# 26_LMS3_RX2_BB_ADC.net
KiCad netlist of a schematic drawn in Altium Designer
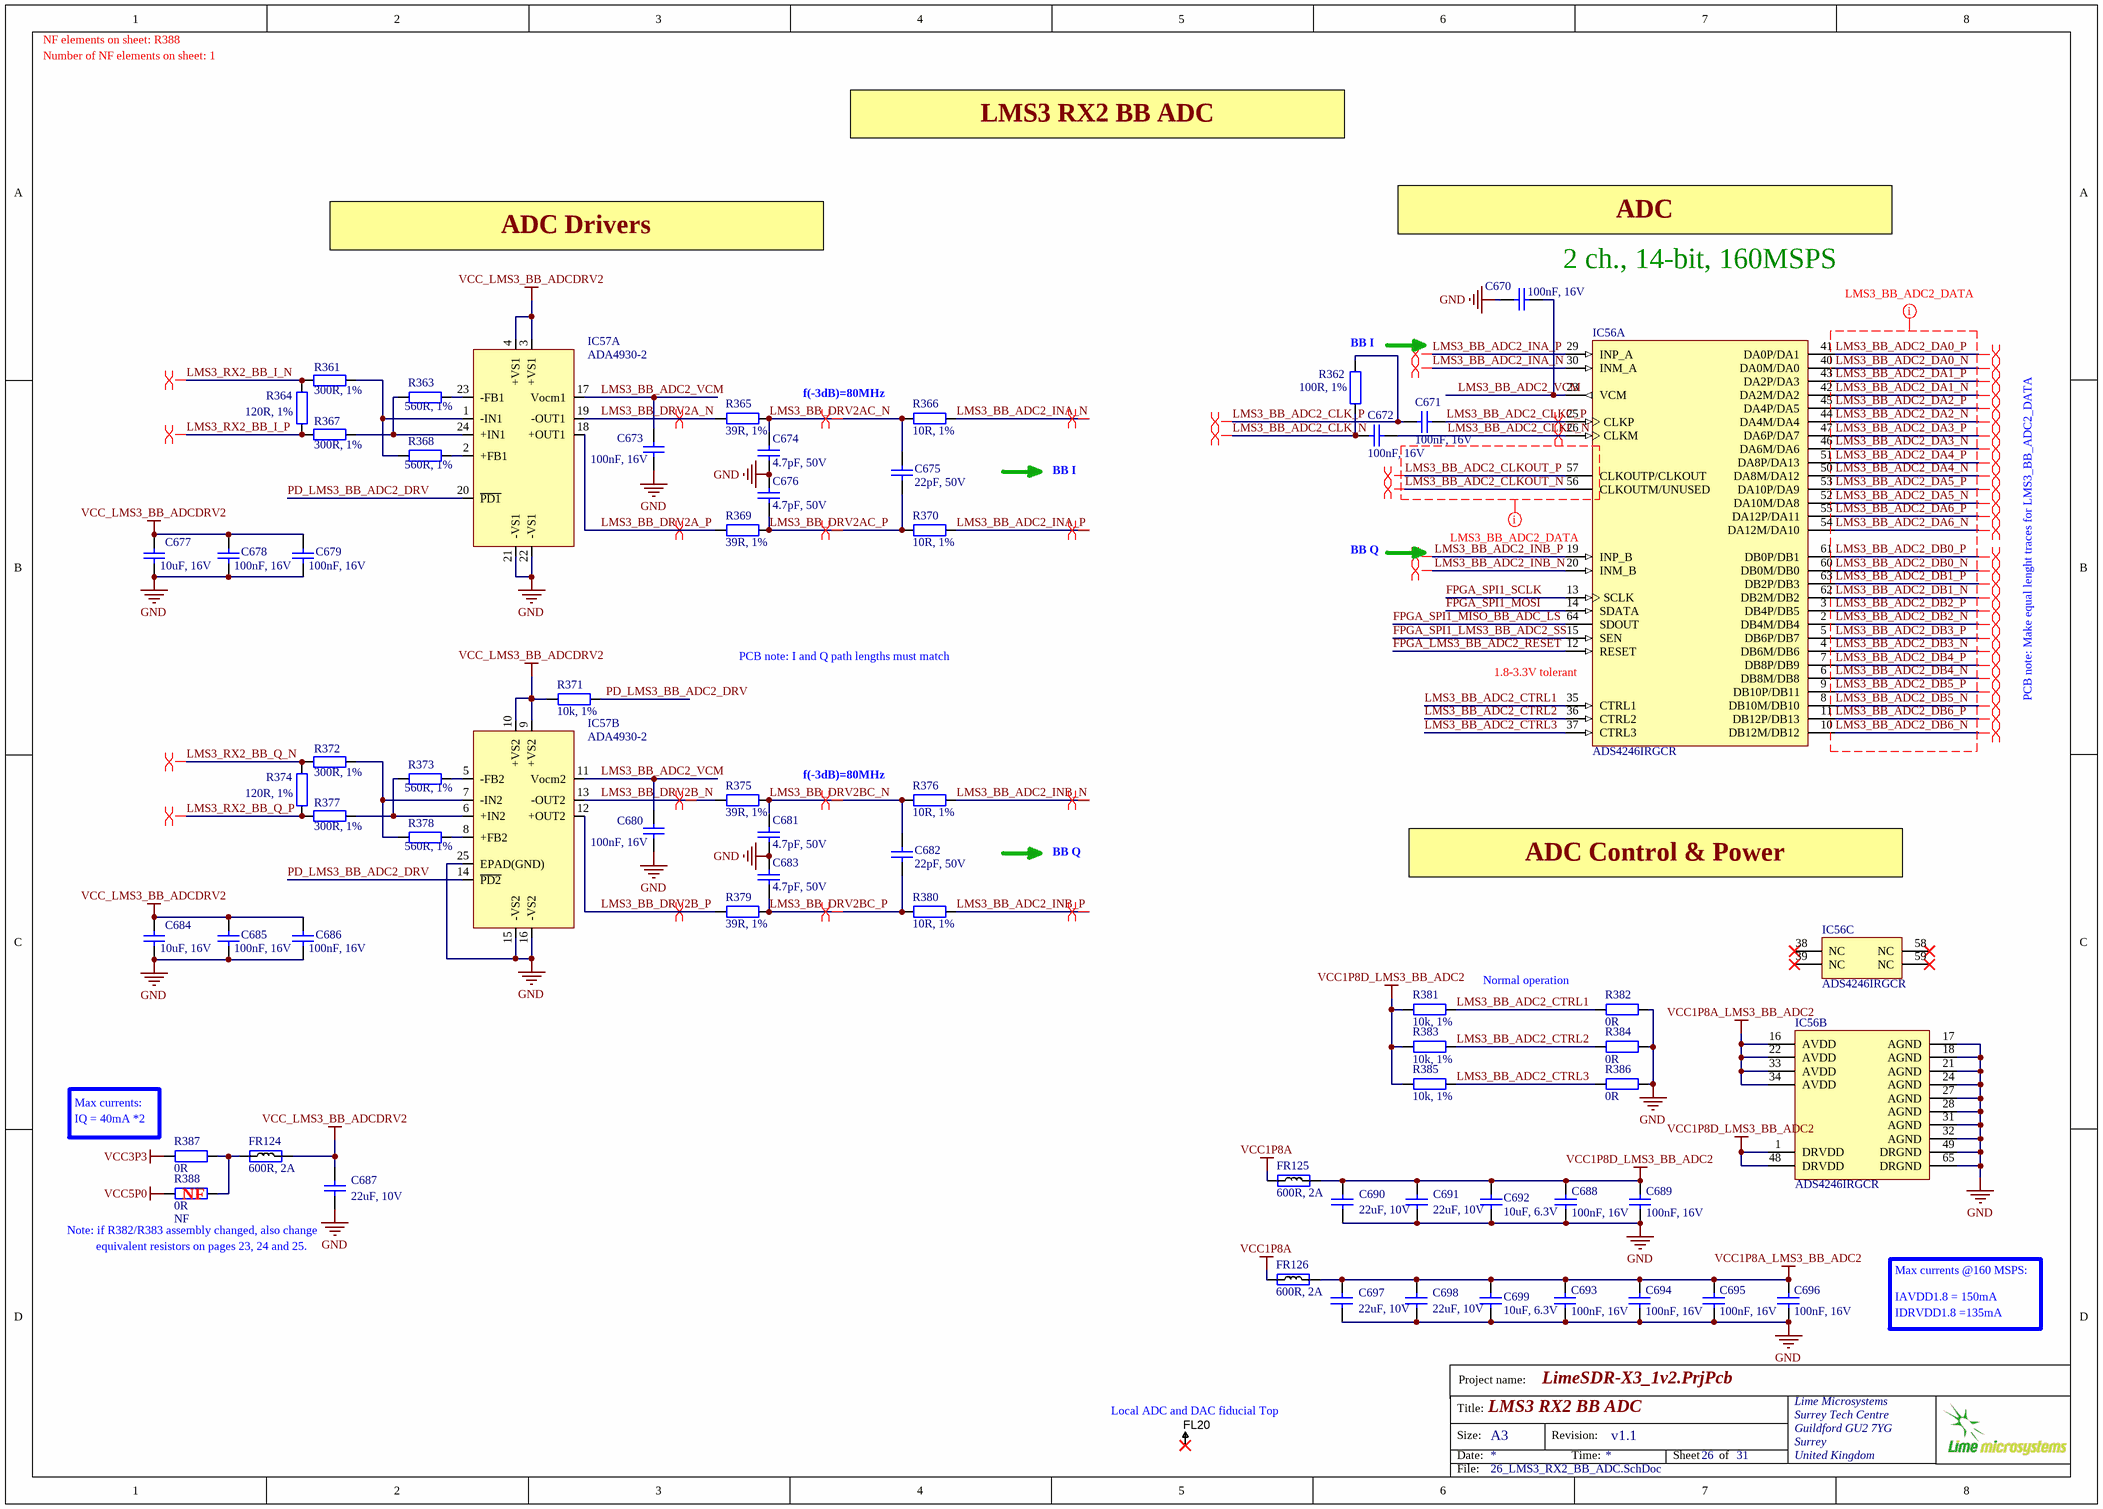
[diagram p0: 26_LMS3_RX2_BB_ADC.SchDoc]

(export (version "E")
  (design (tool "Eeschema 10.0.6"))
  (components
    (comp (ref "C670")
      (value "100nF, 16V")
      (footprint "CAP0402")
      (fields (field (name "TOLERANCE") "10 %") (field (name "MANUFACTURER") "Murata Electronics"))
      (libsource (lib "") (part "Cap_0603_3"))
    )
    (comp (ref "C671")
      (value "100nF, 16V")
      (footprint "CAP0402")
      (fields (field (name "TOLERANCE") "10 %") (field (name "MANUFACTURER") "Murata Electronics"))
      (libsource (lib "") (part "Cap_0603_3"))
    )
    (comp (ref "C672")
      (value "100nF, 16V")
      (footprint "CAP0402")
      (fields (field (name "TOLERANCE") "10 %") (field (name "MANUFACTURER") "Murata Electronics"))
      (libsource (lib "LimeFPGAboard_schLib") (part "Cap_0603"))
    )
    (comp (ref "C673")
      (value "100nF, 16V")
      (footprint "CAP0402")
      (fields (field (name "TOLERANCE") "10 %") (field (name "MANUFACTURER") "Murata Electronics"))
      (libsource (lib "LimeFPGAboard_schLib") (part "Cap_0603"))
    )
    (comp (ref "C674")
      (value "4.7pF, 50V")
      (footprint "CAP0402")
      (fields (field (name "MANUFACTURER") "MURATA"))
      (libsource (lib "") (part "Cap_0402_1"))
    )
    (comp (ref "C675")
      (value "22pF, 50V")
      (footprint "CAP0402")
      (fields (field (name "TOLERANCE") "±5%") (field (name "MANUFACTURER") "Yageo"))
      (libsource (lib "LimeMicroAltiumLib_schLib") (part "Cap_0402"))
    )
    (comp (ref "C676")
      (value "4.7pF, 50V")
      (footprint "CAP0402")
      (fields (field (name "MANUFACTURER") "MURATA"))
      (libsource (lib "") (part "Cap_0402_1"))
    )
    (comp (ref "C677")
      (value "10uF, 16V")
      (footprint "CAP0603")
      (fields (field (name "MANUFACTURER") "Yageo") (field (name "TOLERANCE") "±20%"))
      (libsource (lib "LimeMicroAltiumLib_schLib") (part "Cap_0603"))
    )
    (comp (ref "C678")
      (value "100nF, 16V")
      (footprint "CAP0402")
      (fields (field (name "TOLERANCE") "10 %") (field (name "MANUFACTURER") "Murata Electronics"))
      (libsource (lib "LimeFPGAboard_schLib") (part "Cap_0603"))
    )
    (comp (ref "C679")
      (value "100nF, 16V")
      (footprint "CAP0402")
      (fields (field (name "TOLERANCE") "10 %") (field (name "MANUFACTURER") "Murata Electronics"))
      (libsource (lib "LimeFPGAboard_schLib") (part "Cap_0603"))
    )
    (comp (ref "C680")
      (value "100nF, 16V")
      (footprint "CAP0402")
      (fields (field (name "TOLERANCE") "10 %") (field (name "MANUFACTURER") "Murata Electronics"))
      (libsource (lib "") (part "Cap_0603_6"))
    )
    (comp (ref "C681")
      (value "4.7pF, 50V")
      (footprint "CAP0402")
      (fields (field (name "MANUFACTURER") "MURATA"))
      (libsource (lib "") (part "Cap_0402_1"))
    )
    (comp (ref "C682")
      (value "22pF, 50V")
      (footprint "CAP0402")
      (fields (field (name "TOLERANCE") "±5%") (field (name "MANUFACTURER") "Yageo"))
      (libsource (lib "LimeMicroAltiumLib_schLib") (part "Cap_0402"))
    )
    (comp (ref "C683")
      (value "4.7pF, 50V")
      (footprint "CAP0402")
      (fields (field (name "MANUFACTURER") "MURATA"))
      (libsource (lib "") (part "Cap_0402_1"))
    )
    (comp (ref "C684")
      (value "10uF, 16V")
      (footprint "CAP0603")
      (fields (field (name "MANUFACTURER") "Yageo") (field (name "TOLERANCE") "±20%"))
      (libsource (lib "LimeMicroAltiumLib_schLib") (part "Cap_0603"))
    )
    (comp (ref "C685")
      (value "100nF, 16V")
      (footprint "CAP0402")
      (fields (field (name "TOLERANCE") "10 %") (field (name "MANUFACTURER") "Murata Electronics"))
      (libsource (lib "LimeFPGAboard_schLib") (part "Cap_0603"))
    )
    (comp (ref "C686")
      (value "100nF, 16V")
      (footprint "CAP0402")
      (fields (field (name "TOLERANCE") "10 %") (field (name "MANUFACTURER") "Murata Electronics"))
      (libsource (lib "LimeFPGAboard_schLib") (part "Cap_0603"))
    )
    (comp (ref "C687")
      (value "22uF, 10V")
      (footprint "CAP0603")
      (fields (field (name "TOLERANCE") "20 %") (field (name "MANUFACTURER") "TDK Corporation"))
      (libsource (lib "") (part "Cap_0603_7"))
    )
    (comp (ref "C688")
      (value "100nF, 16V")
      (footprint "CAP0402")
      (fields (field (name "TOLERANCE") "10 %") (field (name "MANUFACTURER") "Murata Electronics"))
      (libsource (lib "") (part "Cap_0603_2"))
    )
    (comp (ref "C689")
      (value "100nF, 16V")
      (footprint "CAP0402")
      (fields (field (name "TOLERANCE") "10 %") (field (name "MANUFACTURER") "Murata Electronics"))
      (libsource (lib "") (part "Cap_0603_2"))
    )
    (comp (ref "C690")
      (value "22uF, 10V")
      (footprint "CAP0603")
      (fields (field (name "TOLERANCE") "20 %") (field (name "MANUFACTURER") "TDK Corporation"))
      (libsource (lib "") (part "Cap_0603_2"))
    )
    (comp (ref "C691")
      (value "22uF, 10V")
      (footprint "CAP0603")
      (fields (field (name "TOLERANCE") "20 %") (field (name "MANUFACTURER") "TDK Corporation"))
      (libsource (lib "") (part "Cap_0603_2"))
    )
    (comp (ref "C692")
      (value "10uF, 6.3V")
      (footprint "CAP0603")
      (fields (field (name "TOLERANCE") "±20%") (field (name "MANUFACTURER") "Yageo"))
      (libsource (lib "") (part "Cap_0603_5"))
    )
    (comp (ref "C693")
      (value "100nF, 16V")
      (footprint "CAP0402")
      (fields (field (name "TOLERANCE") "10 %") (field (name "MANUFACTURER") "Murata Electronics"))
      (libsource (lib "") (part "Cap_0603_1"))
    )
    (comp (ref "C694")
      (value "100nF, 16V")
      (footprint "CAP0402")
      (fields (field (name "TOLERANCE") "10 %") (field (name "MANUFACTURER") "Murata Electronics"))
      (libsource (lib "") (part "Cap_0603_1"))
    )
    (comp (ref "C695")
      (value "100nF, 16V")
      (footprint "CAP0402")
      (fields (field (name "TOLERANCE") "10 %") (field (name "MANUFACTURER") "Murata Electronics"))
      (libsource (lib "") (part "Cap_0603_1"))
    )
    (comp (ref "C696")
      (value "100nF, 16V")
      (footprint "CAP0402")
      (fields (field (name "TOLERANCE") "10 %") (field (name "MANUFACTURER") "Murata Electronics"))
      (libsource (lib "") (part "Cap_0603_1"))
    )
    (comp (ref "C697")
      (value "22uF, 10V")
      (footprint "CAP0603")
      (fields (field (name "TOLERANCE") "20 %") (field (name "MANUFACTURER") "TDK Corporation"))
      (libsource (lib "") (part "Cap_0603_1"))
    )
    (comp (ref "C698")
      (value "22uF, 10V")
      (footprint "CAP0603")
      (fields (field (name "TOLERANCE") "20 %") (field (name "MANUFACTURER") "TDK Corporation"))
      (libsource (lib "") (part "Cap_0603_1"))
    )
    (comp (ref "C699")
      (value "10uF, 6.3V")
      (footprint "CAP0603")
      (fields (field (name "TOLERANCE") "±20%") (field (name "MANUFACTURER") "Yageo"))
      (libsource (lib "") (part "Cap_0603_4"))
    )
    (comp (ref "FL20")
      (value "Fiducial")
      (footprint "Fiducial_local")
      (libsource (lib "LimeMicroAltiumLib_schLib") (part "Fiducial"))
    )
    (comp (ref "FR124")
      (value "600R, 2A")
      (footprint "RES0805")
      (fields (field (name "MANUFACTURER") "TDK Corporation"))
      (libsource (lib "LimeMicroAltiumLib_schLib") (part "Ferrite"))
    )
    (comp (ref "FR125")
      (value "600R, 2A")
      (footprint "RES0805")
      (fields (field (name "MANUFACTURER") "TDK Corporation"))
      (libsource (lib "LimeFPGAboard_schLib") (part "Ferrite"))
    )
    (comp (ref "FR126")
      (value "600R, 2A")
      (footprint "RES0805")
      (fields (field (name "MANUFACTURER") "TDK Corporation"))
      (libsource (lib "LimeFPGAboard_schLib") (part "Ferrite"))
    )
    (comp (ref "IC56")
      (value "ADS4246IRGCR")
      (footprint "TI-RGC64-7400X7400TP_V")
      (description "14-Bit 160 MSPS Dual Low Power ADC, -40 to 85 degC, 64-pin QFN (RGC64), Green (RoHS & no Sb/Br)")
      (fields (field (name "MANUFACTURER") "Texas Instruments"))
      (libsource (lib "") (part "ADS4246IRGCR_1"))
    )
    (comp (ref "IC57")
      (value "ADA4930-2")
      (footprint "ADA4930-2_LFCSP-24")
      (fields (field (name "MANUFACTURER") "Analog Devices Inc."))
      (libsource (lib "") (part "ADA4930-2_1"))
    )
    (comp (ref "R361")
      (value "300R, 1%")
      (footprint "RES0402")
      (fields (field (name "TOLERANCE") "±1%") (field (name "MANUFACTURER") "Vishay Dale"))
      (libsource (lib "") (part "Res_0402_1"))
    )
    (comp (ref "R362")
      (value "100R, 1%")
      (footprint "RES0402")
      (fields (field (name "TOLERANCE") "±1%") (field (name "MANUFACTURER") "Stackpole Electronics Inc."))
      (libsource (lib "") (part "Res_0402_1"))
    )
    (comp (ref "R363")
      (value "560R, 1%")
      (footprint "RES0402")
      (fields (field (name "TOLERANCE") "±1%") (field (name "MANUFACTURER") "Vishay Dale"))
      (libsource (lib "") (part "Res_0402_1"))
    )
    (comp (ref "R364")
      (value "120R, 1%")
      (footprint "RES0402")
      (fields (field (name "MANUFACTURER") "Yageo") (field (name "TOLERANCE") "1%"))
      (libsource (lib "LimeFPGAboard_schLib") (part "Res_0402"))
    )
    (comp (ref "R365")
      (value "39R, 1%")
      (footprint "RES0402")
      (fields (field (name "MANUFACTURER") "Yageo") (field (name "TOLERANCE") "1%"))
      (libsource (lib "LimeMicroAltiumLib_schLib") (part "Res_0402"))
    )
    (comp (ref "R366")
      (value "10R, 1%")
      (footprint "RES0402")
      (fields (field (name "TOLERANCE") "1%"))
      (libsource (lib "LimeMicroAltiumLib_schLib") (part "Res_0402"))
    )
    (comp (ref "R367")
      (value "300R, 1%")
      (footprint "RES0402")
      (fields (field (name "TOLERANCE") "±1%") (field (name "MANUFACTURER") "Vishay Dale"))
      (libsource (lib "") (part "Res_0402_1"))
    )
    (comp (ref "R368")
      (value "560R, 1%")
      (footprint "RES0402")
      (fields (field (name "TOLERANCE") "±1%") (field (name "MANUFACTURER") "Vishay Dale"))
      (libsource (lib "") (part "Res_0402_1"))
    )
    (comp (ref "R369")
      (value "39R, 1%")
      (footprint "RES0402")
      (fields (field (name "MANUFACTURER") "Yageo") (field (name "TOLERANCE") "1%"))
      (libsource (lib "LimeMicroAltiumLib_schLib") (part "Res_0402"))
    )
    (comp (ref "R370")
      (value "10R, 1%")
      (footprint "RES0402")
      (fields (field (name "TOLERANCE") "1%"))
      (libsource (lib "LimeMicroAltiumLib_schLib") (part "Res_0402"))
    )
    (comp (ref "R371")
      (value "10k, 1%")
      (footprint "RES0402")
      (fields (field (name "MANUFACTURER") "Yageo") (field (name "TOLERANCE") "±1%"))
      (libsource (lib "LimeMicroAltiumLib_schLib") (part "Res_0402"))
    )
    (comp (ref "R372")
      (value "300R, 1%")
      (footprint "RES0402")
      (fields (field (name "TOLERANCE") "±1%") (field (name "MANUFACTURER") "Vishay Dale"))
      (libsource (lib "") (part "Res_0402_1"))
    )
    (comp (ref "R373")
      (value "560R, 1%")
      (footprint "RES0402")
      (fields (field (name "TOLERANCE") "±1%") (field (name "MANUFACTURER") "Vishay Dale"))
      (libsource (lib "") (part "Res_0402_1"))
    )
    (comp (ref "R374")
      (value "120R, 1%")
      (footprint "RES0402")
      (fields (field (name "MANUFACTURER") "Yageo") (field (name "TOLERANCE") "1%"))
      (libsource (lib "LimeFPGAboard_schLib") (part "Res_0402"))
    )
    (comp (ref "R375")
      (value "39R, 1%")
      (footprint "RES0402")
      (fields (field (name "MANUFACTURER") "Yageo") (field (name "TOLERANCE") "1%"))
      (libsource (lib "LimeMicroAltiumLib_schLib") (part "Res_0402"))
    )
    (comp (ref "R376")
      (value "10R, 1%")
      (footprint "RES0402")
      (fields (field (name "TOLERANCE") "1%"))
      (libsource (lib "LimeMicroAltiumLib_schLib") (part "Res_0402"))
    )
    (comp (ref "R377")
      (value "300R, 1%")
      (footprint "RES0402")
      (fields (field (name "TOLERANCE") "±1%") (field (name "MANUFACTURER") "Vishay Dale"))
      (libsource (lib "") (part "Res_0402_1"))
    )
    (comp (ref "R378")
      (value "560R, 1%")
      (footprint "RES0402")
      (fields (field (name "TOLERANCE") "±1%") (field (name "MANUFACTURER") "Vishay Dale"))
      (libsource (lib "") (part "Res_0402_1"))
    )
    (comp (ref "R379")
      (value "39R, 1%")
      (footprint "RES0402")
      (fields (field (name "MANUFACTURER") "Yageo") (field (name "TOLERANCE") "1%"))
      (libsource (lib "LimeMicroAltiumLib_schLib") (part "Res_0402"))
    )
    (comp (ref "R380")
      (value "10R, 1%")
      (footprint "RES0402")
      (fields (field (name "TOLERANCE") "1%"))
      (libsource (lib "LimeMicroAltiumLib_schLib") (part "Res_0402"))
    )
    (comp (ref "R381")
      (value "10k, 1%")
      (footprint "RES0402")
      (fields (field (name "MANUFACTURER") "Yageo") (field (name "TOLERANCE") "±1%"))
      (libsource (lib "LimeMicroAltiumLib_schLib") (part "Res_0402"))
    )
    (comp (ref "R382")
      (value "0R")
      (footprint "RES0402")
      (fields (field (name "MANUFACTURER") "Yageo"))
      (libsource (lib "") (part "Res_0402_1"))
    )
    (comp (ref "R383")
      (value "10k, 1%")
      (footprint "RES0402")
      (fields (field (name "MANUFACTURER") "Yageo") (field (name "TOLERANCE") "±1%"))
      (libsource (lib "LimeMicroAltiumLib_schLib") (part "Res_0402"))
    )
    (comp (ref "R384")
      (value "0R")
      (footprint "RES0402")
      (fields (field (name "MANUFACTURER") "Yageo"))
      (libsource (lib "") (part "Res_0402_1"))
    )
    (comp (ref "R385")
      (value "10k, 1%")
      (footprint "RES0402")
      (fields (field (name "MANUFACTURER") "Yageo") (field (name "TOLERANCE") "±1%"))
      (libsource (lib "LimeMicroAltiumLib_schLib") (part "Res_0402"))
    )
    (comp (ref "R386")
      (value "0R")
      (footprint "RES0402")
      (fields (field (name "MANUFACTURER") "Yageo"))
      (libsource (lib "") (part "Res_0402_1"))
    )
    (comp (ref "R387")
      (value "0R")
      (footprint "RES0402")
      (fields (field (name "MANUFACTURER") "Yageo") (field (name "TOLERANCE") "Jumper"))
      (libsource (lib "LimeMicroAltiumLib_schLib") (part "Res_0402"))
    )
    (comp (ref "R388")
      (value "0R")
      (footprint "RES0402")
      (fields
        (field (name "ASSEMBLY INFO") "NF")
        (field (name "MANUFACTURER") "Yageo")
        (field (name "TOLERANCE") "Jumper")
      )
      (libsource (lib "LimeMicroAltiumLib_schLib") (part "Res_0402"))
    )
  )
  (nets
    (net (code "1") (name "/FPGA_LMS3_BB_ADC2_RESET") (class "Default")
      (node (ref "IC56") (pin "12") (pinfunction "RESET_12") (pintype "input"))
    )
    (net (code "2") (name "/FPGA_SPI1_LMS3_BB_ADC2_SS") (class "Default")
      (node (ref "IC56") (pin "15") (pinfunction "SEN_15") (pintype "input"))
    )
    (net (code "3") (name "/FPGA_SPI1_MISO_BB_ADC_LS") (class "Default")
      (node (ref "IC56") (pin "64") (pinfunction "SDOUT_64") (pintype "tri_state"))
    )
    (net (code "4") (name "/FPGA_SPI1_MOSI") (class "Default")
      (node (ref "IC56") (pin "14") (pinfunction "SDATA_14") (pintype "input"))
    )
    (net (code "5") (name "/FPGA_SPI1_SCLK") (class "Default")
      (node (ref "IC56") (pin "13") (pinfunction "SCLK_13") (pintype "input"))
    )
    (net (code "6") (name "/LMS3_BB_ADC2_CLKC_N") (class "Default")
      (node (ref "C672") (pin "1") (pinfunction "1_1") (pintype "passive"))
      (node (ref "IC56") (pin "26") (pinfunction "CLKM_26") (pintype "input"))
    )
    (net (code "7") (name "/LMS3_BB_ADC2_CLKC_P") (class "Default")
      (node (ref "C671") (pin "1") (pinfunction "1_1") (pintype "passive"))
      (node (ref "IC56") (pin "25") (pinfunction "CLKP_25") (pintype "input"))
    )
    (net (code "8") (name "/LMS3_BB_ADC2_CLKOUT_N") (class "Default")
      (node (ref "IC56") (pin "56") (pinfunction "CLKOUTM/UNUSED_56") (pintype "tri_state"))
    )
    (net (code "9") (name "/LMS3_BB_ADC2_CLKOUT_P") (class "Default")
      (node (ref "IC56") (pin "57") (pinfunction "CLKOUTP/CLKOUT_57") (pintype "tri_state"))
    )
    (net (code "10") (name "/LMS3_BB_ADC2_CLK_N") (class "Default")
      (node (ref "C672") (pin "2") (pinfunction "2_2") (pintype "passive"))
      (node (ref "R362") (pin "1") (pinfunction "1_1") (pintype "passive"))
    )
    (net (code "11") (name "/LMS3_BB_ADC2_CLK_P") (class "Default")
      (node (ref "C671") (pin "2") (pinfunction "2_2") (pintype "passive"))
      (node (ref "R362") (pin "2") (pinfunction "2_2") (pintype "passive"))
    )
    (net (code "12") (name "/LMS3_BB_ADC2_CTRL1") (class "Default")
      (node (ref "IC56") (pin "35") (pinfunction "CTRL1_35") (pintype "input"))
      (node (ref "R381") (pin "1") (pinfunction "1_1") (pintype "passive"))
      (node (ref "R382") (pin "2") (pinfunction "2_2") (pintype "passive"))
    )
    (net (code "13") (name "/LMS3_BB_ADC2_CTRL2") (class "Default")
      (node (ref "IC56") (pin "36") (pinfunction "CTRL2_36") (pintype "input"))
      (node (ref "R383") (pin "1") (pinfunction "1_1") (pintype "passive"))
      (node (ref "R384") (pin "2") (pinfunction "2_2") (pintype "passive"))
    )
    (net (code "14") (name "/LMS3_BB_ADC2_CTRL3") (class "Default")
      (node (ref "IC56") (pin "37") (pinfunction "CTRL3_37") (pintype "input"))
      (node (ref "R385") (pin "1") (pinfunction "1_1") (pintype "passive"))
      (node (ref "R386") (pin "2") (pinfunction "2_2") (pintype "passive"))
    )
    (net (code "15") (name "/LMS3_BB_ADC2_DA0_N") (class "Default")
      (node (ref "IC56") (pin "40") (pinfunction "DA0M/DA0_40") (pintype "tri_state"))
    )
    (net (code "16") (name "/LMS3_BB_ADC2_DA0_P") (class "Default")
      (node (ref "IC56") (pin "41") (pinfunction "DA0P/DA1_41") (pintype "tri_state"))
    )
    (net (code "17") (name "/LMS3_BB_ADC2_DA1_N") (class "Default")
      (node (ref "IC56") (pin "42") (pinfunction "DA2M/DA2_42") (pintype "tri_state"))
    )
    (net (code "18") (name "/LMS3_BB_ADC2_DA1_P") (class "Default")
      (node (ref "IC56") (pin "43") (pinfunction "DA2P/DA3_43") (pintype "tri_state"))
    )
    (net (code "19") (name "/LMS3_BB_ADC2_DA2_N") (class "Default")
      (node (ref "IC56") (pin "44") (pinfunction "DA4M/DA4_44") (pintype "tri_state"))
    )
    (net (code "20") (name "/LMS3_BB_ADC2_DA2_P") (class "Default")
      (node (ref "IC56") (pin "45") (pinfunction "DA4P/DA5_45") (pintype "tri_state"))
    )
    (net (code "21") (name "/LMS3_BB_ADC2_DA3_N") (class "Default")
      (node (ref "IC56") (pin "46") (pinfunction "DA6M/DA6_46") (pintype "tri_state"))
    )
    (net (code "22") (name "/LMS3_BB_ADC2_DA3_P") (class "Default")
      (node (ref "IC56") (pin "47") (pinfunction "DA6P/DA7_47") (pintype "tri_state"))
    )
    (net (code "23") (name "/LMS3_BB_ADC2_DA4_N") (class "Default")
      (node (ref "IC56") (pin "50") (pinfunction "DA8M/DA12_50") (pintype "tri_state"))
    )
    (net (code "24") (name "/LMS3_BB_ADC2_DA4_P") (class "Default")
      (node (ref "IC56") (pin "51") (pinfunction "DA8P/DA13_51") (pintype "tri_state"))
    )
    (net (code "25") (name "/LMS3_BB_ADC2_DA5_N") (class "Default")
      (node (ref "IC56") (pin "52") (pinfunction "DA10M/DA8_52") (pintype "tri_state"))
    )
    (net (code "26") (name "/LMS3_BB_ADC2_DA5_P") (class "Default")
      (node (ref "IC56") (pin "53") (pinfunction "DA10P/DA9_53") (pintype "tri_state"))
    )
    (net (code "27") (name "/LMS3_BB_ADC2_DA6_N") (class "Default")
      (node (ref "IC56") (pin "54") (pinfunction "DA12M/DA10_54") (pintype "tri_state"))
    )
    (net (code "28") (name "/LMS3_BB_ADC2_DA6_P") (class "Default")
      (node (ref "IC56") (pin "55") (pinfunction "DA12P/DA11_55") (pintype "tri_state"))
    )
    (net (code "29") (name "/LMS3_BB_ADC2_DB0_N") (class "Default")
      (node (ref "IC56") (pin "60") (pinfunction "DB0M/DB0_60") (pintype "tri_state"))
    )
    (net (code "30") (name "/LMS3_BB_ADC2_DB0_P") (class "Default")
      (node (ref "IC56") (pin "61") (pinfunction "DB0P/DB1_61") (pintype "tri_state"))
    )
    (net (code "31") (name "/LMS3_BB_ADC2_DB1_N") (class "Default")
      (node (ref "IC56") (pin "62") (pinfunction "DB2M/DB2_62") (pintype "tri_state"))
    )
    (net (code "32") (name "/LMS3_BB_ADC2_DB1_P") (class "Default")
      (node (ref "IC56") (pin "63") (pinfunction "DB2P/DB3_63") (pintype "tri_state"))
    )
    (net (code "33") (name "/LMS3_BB_ADC2_DB2_N") (class "Default")
      (node (ref "IC56") (pin "2") (pinfunction "DB4M/DB4_2") (pintype "tri_state"))
    )
    (net (code "34") (name "/LMS3_BB_ADC2_DB2_P") (class "Default")
      (node (ref "IC56") (pin "3") (pinfunction "DB4P/DB5_3") (pintype "tri_state"))
    )
    (net (code "35") (name "/LMS3_BB_ADC2_DB3_N") (class "Default")
      (node (ref "IC56") (pin "4") (pinfunction "DB6M/DB6_4") (pintype "tri_state"))
    )
    (net (code "36") (name "/LMS3_BB_ADC2_DB3_P") (class "Default")
      (node (ref "IC56") (pin "5") (pinfunction "DB6P/DB7_5") (pintype "tri_state"))
    )
    (net (code "37") (name "/LMS3_BB_ADC2_DB4_N") (class "Default")
      (node (ref "IC56") (pin "6") (pinfunction "DB8M/DB8_6") (pintype "tri_state"))
    )
    (net (code "38") (name "/LMS3_BB_ADC2_DB4_P") (class "Default")
      (node (ref "IC56") (pin "7") (pinfunction "DB8P/DB9_7") (pintype "tri_state"))
    )
    (net (code "39") (name "/LMS3_BB_ADC2_DB5_N") (class "Default")
      (node (ref "IC56") (pin "8") (pinfunction "DB10M/DB10_8") (pintype "tri_state"))
    )
    (net (code "40") (name "/LMS3_BB_ADC2_DB5_P") (class "Default")
      (node (ref "IC56") (pin "9") (pinfunction "DB10P/DB11_9") (pintype "tri_state"))
    )
    (net (code "41") (name "/LMS3_BB_ADC2_DB6_N") (class "Default")
      (node (ref "IC56") (pin "10") (pinfunction "DB12M/DB12_10") (pintype "tri_state"))
    )
    (net (code "42") (name "/LMS3_BB_ADC2_DB6_P") (class "Default")
      (node (ref "IC56") (pin "11") (pinfunction "DB12P/DB13_11") (pintype "tri_state"))
    )
    (net (code "43") (name "/LMS3_BB_ADC2_INA_N") (class "Default")
      (node (ref "IC56") (pin "30") (pinfunction "INM_A_30") (pintype "input"))
      (node (ref "R366") (pin "1") (pinfunction "1_1") (pintype "passive"))
    )
    (net (code "44") (name "/LMS3_BB_ADC2_INA_P") (class "Default")
      (node (ref "IC56") (pin "29") (pinfunction "INP_A_29") (pintype "input"))
      (node (ref "R370") (pin "1") (pinfunction "1_1") (pintype "passive"))
    )
    (net (code "45") (name "/LMS3_BB_ADC2_INB_N") (class "Default")
      (node (ref "IC56") (pin "20") (pinfunction "INM_B_20") (pintype "input"))
      (node (ref "R376") (pin "1") (pinfunction "1_1") (pintype "passive"))
    )
    (net (code "46") (name "/LMS3_BB_ADC2_INB_P") (class "Default")
      (node (ref "IC56") (pin "19") (pinfunction "INP_B_19") (pintype "input"))
      (node (ref "R380") (pin "1") (pinfunction "1_1") (pintype "passive"))
    )
    (net (code "47") (name "/LMS3_BB_ADC2_VCM") (class "Default")
      (node (ref "C670") (pin "2") (pinfunction "2_2") (pintype "passive"))
      (node (ref "C673") (pin "1") (pinfunction "1_1") (pintype "passive"))
      (node (ref "C680") (pin "1") (pinfunction "1_1") (pintype "passive"))
      (node (ref "IC56") (pin "23") (pinfunction "VCM_23") (pintype "output"))
      (node (ref "IC57") (pin "11") (pinfunction "Vocm2_11") (pintype "input"))
      (node (ref "IC57") (pin "17") (pinfunction "Vocm1_17") (pintype "input"))
    )
    (net (code "48") (name "/LMS3_BB_DRV2AC_N") (class "Default")
      (node (ref "C674") (pin "1") (pinfunction "1_1") (pintype "passive"))
      (node (ref "C675") (pin "1") (pinfunction "1_1") (pintype "passive"))
      (node (ref "R365") (pin "1") (pinfunction "1_1") (pintype "passive"))
      (node (ref "R366") (pin "2") (pinfunction "2_2") (pintype "passive"))
    )
    (net (code "49") (name "/LMS3_BB_DRV2AC_P") (class "Default")
      (node (ref "C675") (pin "2") (pinfunction "2_2") (pintype "passive"))
      (node (ref "C676") (pin "2") (pinfunction "2_2") (pintype "passive"))
      (node (ref "R369") (pin "1") (pinfunction "1_1") (pintype "passive"))
      (node (ref "R370") (pin "2") (pinfunction "2_2") (pintype "passive"))
    )
    (net (code "50") (name "/LMS3_BB_DRV2A_N") (class "Default")
      (node (ref "IC57") (pin "19") (pinfunction "-OUT1_19") (pintype "output"))
      (node (ref "R365") (pin "2") (pinfunction "2_2") (pintype "passive"))
    )
    (net (code "51") (name "/LMS3_BB_DRV2A_P") (class "Default")
      (node (ref "IC57") (pin "18") (pinfunction "+OUT1_18") (pintype "output"))
      (node (ref "R369") (pin "2") (pinfunction "2_2") (pintype "passive"))
    )
    (net (code "52") (name "/LMS3_BB_DRV2BC_N") (class "Default")
      (node (ref "C681") (pin "1") (pinfunction "1_1") (pintype "passive"))
      (node (ref "C682") (pin "1") (pinfunction "1_1") (pintype "passive"))
      (node (ref "R375") (pin "1") (pinfunction "1_1") (pintype "passive"))
      (node (ref "R376") (pin "2") (pinfunction "2_2") (pintype "passive"))
    )
    (net (code "53") (name "/LMS3_BB_DRV2BC_P") (class "Default")
      (node (ref "C682") (pin "2") (pinfunction "2_2") (pintype "passive"))
      (node (ref "C683") (pin "2") (pinfunction "2_2") (pintype "passive"))
      (node (ref "R379") (pin "1") (pinfunction "1_1") (pintype "passive"))
      (node (ref "R380") (pin "2") (pinfunction "2_2") (pintype "passive"))
    )
    (net (code "54") (name "/LMS3_BB_DRV2B_N") (class "Default")
      (node (ref "IC57") (pin "13") (pinfunction "-OUT2_13") (pintype "output"))
      (node (ref "R375") (pin "2") (pinfunction "2_2") (pintype "passive"))
    )
    (net (code "55") (name "/LMS3_BB_DRV2B_P") (class "Default")
      (node (ref "IC57") (pin "12") (pinfunction "+OUT2_12") (pintype "output"))
      (node (ref "R379") (pin "2") (pinfunction "2_2") (pintype "passive"))
    )
    (net (code "56") (name "/LMS3_RX2_BB_I_N") (class "Default")
      (node (ref "R361") (pin "2") (pinfunction "2_2") (pintype "passive"))
      (node (ref "R364") (pin "2") (pinfunction "2_2") (pintype "passive"))
    )
    (net (code "57") (name "/LMS3_RX2_BB_I_P") (class "Default")
      (node (ref "R364") (pin "1") (pinfunction "1_1") (pintype "passive"))
      (node (ref "R367") (pin "2") (pinfunction "2_2") (pintype "passive"))
    )
    (net (code "58") (name "/LMS3_RX2_BB_Q_N") (class "Default")
      (node (ref "R372") (pin "2") (pinfunction "2_2") (pintype "passive"))
      (node (ref "R374") (pin "2") (pinfunction "2_2") (pintype "passive"))
    )
    (net (code "59") (name "/LMS3_RX2_BB_Q_P") (class "Default")
      (node (ref "R374") (pin "1") (pinfunction "1_1") (pintype "passive"))
      (node (ref "R377") (pin "2") (pinfunction "2_2") (pintype "passive"))
    )
    (net (code "60") (name "/PD_LMS3_BB_ADC2_DRV") (class "Default")
      (node (ref "IC57") (pin "14") (pinfunction "~{PD2}_14") (pintype "input"))
      (node (ref "IC57") (pin "20") (pinfunction "~{PD1}_20") (pintype "input"))
      (node (ref "R371") (pin "1") (pinfunction "1_1") (pintype "passive"))
    )
    (net (code "61") (name "GND") (class "Default")
      (node (ref "C670") (pin "1") (pinfunction "1_1") (pintype "passive"))
      (node (ref "C673") (pin "2") (pinfunction "2_2") (pintype "passive"))
      (node (ref "C674") (pin "2") (pinfunction "2_2") (pintype "passive"))
      (node (ref "C676") (pin "1") (pinfunction "1_1") (pintype "passive"))
      (node (ref "C677") (pin "1") (pinfunction "1_1") (pintype "passive"))
      (node (ref "C678") (pin "2") (pinfunction "2_2") (pintype "passive"))
      (node (ref "C679") (pin "2") (pinfunction "2_2") (pintype "passive"))
      (node (ref "C680") (pin "2") (pinfunction "2_2") (pintype "passive"))
      (node (ref "C681") (pin "2") (pinfunction "2_2") (pintype "passive"))
      (node (ref "C683") (pin "1") (pinfunction "1_1") (pintype "passive"))
      (node (ref "C684") (pin "1") (pinfunction "1_1") (pintype "passive"))
      (node (ref "C685") (pin "2") (pinfunction "2_2") (pintype "passive"))
      (node (ref "C686") (pin "2") (pinfunction "2_2") (pintype "passive"))
      (node (ref "C687") (pin "1") (pinfunction "1_1") (pintype "passive"))
      (node (ref "C688") (pin "1") (pinfunction "1_1") (pintype "passive"))
      (node (ref "C689") (pin "1") (pinfunction "1_1") (pintype "passive"))
      (node (ref "C690") (pin "1") (pinfunction "1_1") (pintype "passive"))
      (node (ref "C691") (pin "1") (pinfunction "1_1") (pintype "passive"))
      (node (ref "C692") (pin "2") (pinfunction "2_2") (pintype "passive"))
      (node (ref "C693") (pin "1") (pinfunction "1_1") (pintype "passive"))
      (node (ref "C694") (pin "1") (pinfunction "1_1") (pintype "passive"))
      (node (ref "C695") (pin "1") (pinfunction "1_1") (pintype "passive"))
      (node (ref "C696") (pin "1") (pinfunction "1_1") (pintype "passive"))
      (node (ref "C697") (pin "1") (pinfunction "1_1") (pintype "passive"))
      (node (ref "C698") (pin "1") (pinfunction "1_1") (pintype "passive"))
      (node (ref "C699") (pin "2") (pinfunction "2_2") (pintype "passive"))
      (node (ref "IC56") (pin "17") (pinfunction "AGND_17") (pintype "power_in"))
      (node (ref "IC56") (pin "18") (pinfunction "AGND_18") (pintype "power_in"))
      (node (ref "IC56") (pin "21") (pinfunction "AGND_21") (pintype "power_in"))
      (node (ref "IC56") (pin "24") (pinfunction "AGND_24") (pintype "power_in"))
      (node (ref "IC56") (pin "27") (pinfunction "AGND_27") (pintype "power_in"))
      (node (ref "IC56") (pin "28") (pinfunction "AGND_28") (pintype "power_in"))
      (node (ref "IC56") (pin "31") (pinfunction "AGND_31") (pintype "power_in"))
      (node (ref "IC56") (pin "32") (pinfunction "AGND_32") (pintype "power_in"))
      (node (ref "IC56") (pin "49") (pinfunction "DRGND_49") (pintype "power_in"))
      (node (ref "IC56") (pin "65") (pinfunction "DRGND_65") (pintype "power_in"))
      (node (ref "IC57") (pin "15") (pinfunction "-VS2_15") (pintype "power_in"))
      (node (ref "IC57") (pin "16") (pinfunction "-VS2_16") (pintype "power_in"))
      (node (ref "IC57") (pin "21") (pinfunction "-VS1_21") (pintype "power_in"))
      (node (ref "IC57") (pin "22") (pinfunction "-VS1_22") (pintype "power_in"))
      (node (ref "IC57") (pin "25") (pinfunction "EPAD(GND)_25") (pintype "passive"))
      (node (ref "R382") (pin "1") (pinfunction "1_1") (pintype "passive"))
      (node (ref "R384") (pin "1") (pinfunction "1_1") (pintype "passive"))
      (node (ref "R386") (pin "1") (pinfunction "1_1") (pintype "passive"))
    )
    (net (code "62") (name "Net-(FR124-Pad1)") (class "Default")
      (node (ref "FR124") (pin "1") (pinfunction "1_1") (pintype "passive"))
      (node (ref "R387") (pin "1") (pinfunction "1_1") (pintype "passive"))
      (node (ref "R388") (pin "1") (pinfunction "1_1") (pintype "passive"))
    )
    (net (code "63") (name "Net-(IC57A-+FB1)") (class "Default")
      (node (ref "IC57") (pin "2") (pinfunction "+FB1_2") (pintype "output"))
      (node (ref "R368") (pin "1") (pinfunction "1_1") (pintype "passive"))
    )
    (net (code "64") (name "Net-(IC57A-+IN1)") (class "Default")
      (node (ref "IC57") (pin "24") (pinfunction "+IN1_24") (pintype "input"))
      (node (ref "R363") (pin "2") (pinfunction "2_2") (pintype "passive"))
      (node (ref "R367") (pin "1") (pinfunction "1_1") (pintype "passive"))
    )
    (net (code "65") (name "Net-(IC57A--FB1)") (class "Default")
      (node (ref "IC57") (pin "23") (pinfunction "-FB1_23") (pintype "output"))
      (node (ref "R363") (pin "1") (pinfunction "1_1") (pintype "passive"))
    )
    (net (code "66") (name "Net-(IC57A--IN1)") (class "Default")
      (node (ref "IC57") (pin "1") (pinfunction "-IN1_1") (pintype "input"))
      (node (ref "R361") (pin "1") (pinfunction "1_1") (pintype "passive"))
      (node (ref "R368") (pin "2") (pinfunction "2_2") (pintype "passive"))
    )
    (net (code "67") (name "Net-(IC57B-+FB2)") (class "Default")
      (node (ref "IC57") (pin "8") (pinfunction "+FB2_8") (pintype "output"))
      (node (ref "R378") (pin "1") (pinfunction "1_1") (pintype "passive"))
    )
    (net (code "68") (name "Net-(IC57B-+IN2)") (class "Default")
      (node (ref "IC57") (pin "6") (pinfunction "+IN2_6") (pintype "input"))
      (node (ref "R373") (pin "2") (pinfunction "2_2") (pintype "passive"))
      (node (ref "R377") (pin "1") (pinfunction "1_1") (pintype "passive"))
    )
    (net (code "69") (name "Net-(IC57B--FB2)") (class "Default")
      (node (ref "IC57") (pin "5") (pinfunction "-FB2_5") (pintype "output"))
      (node (ref "R373") (pin "1") (pinfunction "1_1") (pintype "passive"))
    )
    (net (code "70") (name "Net-(IC57B--IN2)") (class "Default")
      (node (ref "IC57") (pin "7") (pinfunction "-IN2_7") (pintype "input"))
      (node (ref "R372") (pin "1") (pinfunction "1_1") (pintype "passive"))
      (node (ref "R378") (pin "2") (pinfunction "2_2") (pintype "passive"))
    )
    (net (code "71") (name "VCC1P8A") (class "Default")
      (node (ref "FR125") (pin "1") (pinfunction "1_1") (pintype "passive"))
      (node (ref "FR126") (pin "1") (pinfunction "1_1") (pintype "passive"))
    )
    (net (code "72") (name "VCC1P8A_LMS3_BB_ADC2") (class "Default")
      (node (ref "C693") (pin "2") (pinfunction "2_2") (pintype "passive"))
      (node (ref "C694") (pin "2") (pinfunction "2_2") (pintype "passive"))
      (node (ref "C695") (pin "2") (pinfunction "2_2") (pintype "passive"))
      (node (ref "C696") (pin "2") (pinfunction "2_2") (pintype "passive"))
      (node (ref "C697") (pin "2") (pinfunction "2_2") (pintype "passive"))
      (node (ref "C698") (pin "2") (pinfunction "2_2") (pintype "passive"))
      (node (ref "C699") (pin "1") (pinfunction "1_1") (pintype "passive"))
      (node (ref "FR126") (pin "2") (pinfunction "2_2") (pintype "passive"))
      (node (ref "IC56") (pin "16") (pinfunction "AVDD_16") (pintype "power_in"))
      (node (ref "IC56") (pin "22") (pinfunction "AVDD_22") (pintype "power_in"))
      (node (ref "IC56") (pin "33") (pinfunction "AVDD_33") (pintype "power_in"))
      (node (ref "IC56") (pin "34") (pinfunction "AVDD_34") (pintype "power_in"))
    )
    (net (code "73") (name "VCC1P8D_LMS3_BB_ADC2") (class "Default")
      (node (ref "C688") (pin "2") (pinfunction "2_2") (pintype "passive"))
      (node (ref "C689") (pin "2") (pinfunction "2_2") (pintype "passive"))
      (node (ref "C690") (pin "2") (pinfunction "2_2") (pintype "passive"))
      (node (ref "C691") (pin "2") (pinfunction "2_2") (pintype "passive"))
      (node (ref "C692") (pin "1") (pinfunction "1_1") (pintype "passive"))
      (node (ref "FR125") (pin "2") (pinfunction "2_2") (pintype "passive"))
      (node (ref "IC56") (pin "1") (pinfunction "DRVDD_1") (pintype "power_in"))
      (node (ref "IC56") (pin "48") (pinfunction "DRVDD_48") (pintype "power_in"))
      (node (ref "R381") (pin "2") (pinfunction "2_2") (pintype "passive"))
      (node (ref "R383") (pin "2") (pinfunction "2_2") (pintype "passive"))
      (node (ref "R385") (pin "2") (pinfunction "2_2") (pintype "passive"))
    )
    (net (code "74") (name "VCC3P3") (class "Default")
      (node (ref "R387") (pin "2") (pinfunction "2_2") (pintype "passive"))
    )
    (net (code "75") (name "VCC5P0") (class "Default")
      (node (ref "R388") (pin "2") (pinfunction "2_2") (pintype "passive"))
    )
    (net (code "76") (name "VCC_LMS3_BB_ADCDRV2") (class "Default")
      (node (ref "C677") (pin "2") (pinfunction "2_2") (pintype "passive"))
      (node (ref "C678") (pin "1") (pinfunction "1_1") (pintype "passive"))
      (node (ref "C679") (pin "1") (pinfunction "1_1") (pintype "passive"))
      (node (ref "C684") (pin "2") (pinfunction "2_2") (pintype "passive"))
      (node (ref "C685") (pin "1") (pinfunction "1_1") (pintype "passive"))
      (node (ref "C686") (pin "1") (pinfunction "1_1") (pintype "passive"))
      (node (ref "C687") (pin "2") (pinfunction "2_2") (pintype "passive"))
      (node (ref "FR124") (pin "2") (pinfunction "2_2") (pintype "passive"))
      (node (ref "IC57") (pin "10") (pinfunction "+VS2_10") (pintype "power_in"))
      (node (ref "IC57") (pin "3") (pinfunction "+VS1_3") (pintype "power_in"))
      (node (ref "IC57") (pin "4") (pinfunction "+VS1_4") (pintype "power_in"))
      (node (ref "IC57") (pin "9") (pinfunction "+VS2_9") (pintype "power_in"))
      (node (ref "R371") (pin "2") (pinfunction "2_2") (pintype "passive"))
    )
    (net (code "77") (name "unconnected-(FL20-Pad1)") (class "Default")
      (node (ref "FL20") (pin "1") (pintype "passive+no_connect"))
    )
    (net (code "78") (name "unconnected-(IC56C-NC-Pad38)") (class "Default")
      (node (ref "IC56") (pin "38") (pinfunction "NC_38") (pintype "passive+no_connect"))
    )
    (net (code "79") (name "unconnected-(IC56C-NC-Pad39)") (class "Default")
      (node (ref "IC56") (pin "39") (pinfunction "NC_39") (pintype "passive+no_connect"))
    )
    (net (code "80") (name "unconnected-(IC56C-NC-Pad58)") (class "Default")
      (node (ref "IC56") (pin "58") (pinfunction "NC_58") (pintype "passive+no_connect"))
    )
    (net (code "81") (name "unconnected-(IC56C-NC-Pad59)") (class "Default")
      (node (ref "IC56") (pin "59") (pinfunction "NC_59") (pintype "passive+no_connect"))
    )
  )
)
